# STORAGE.net
KiCad netlist of a schematic drawn in Altium Designer
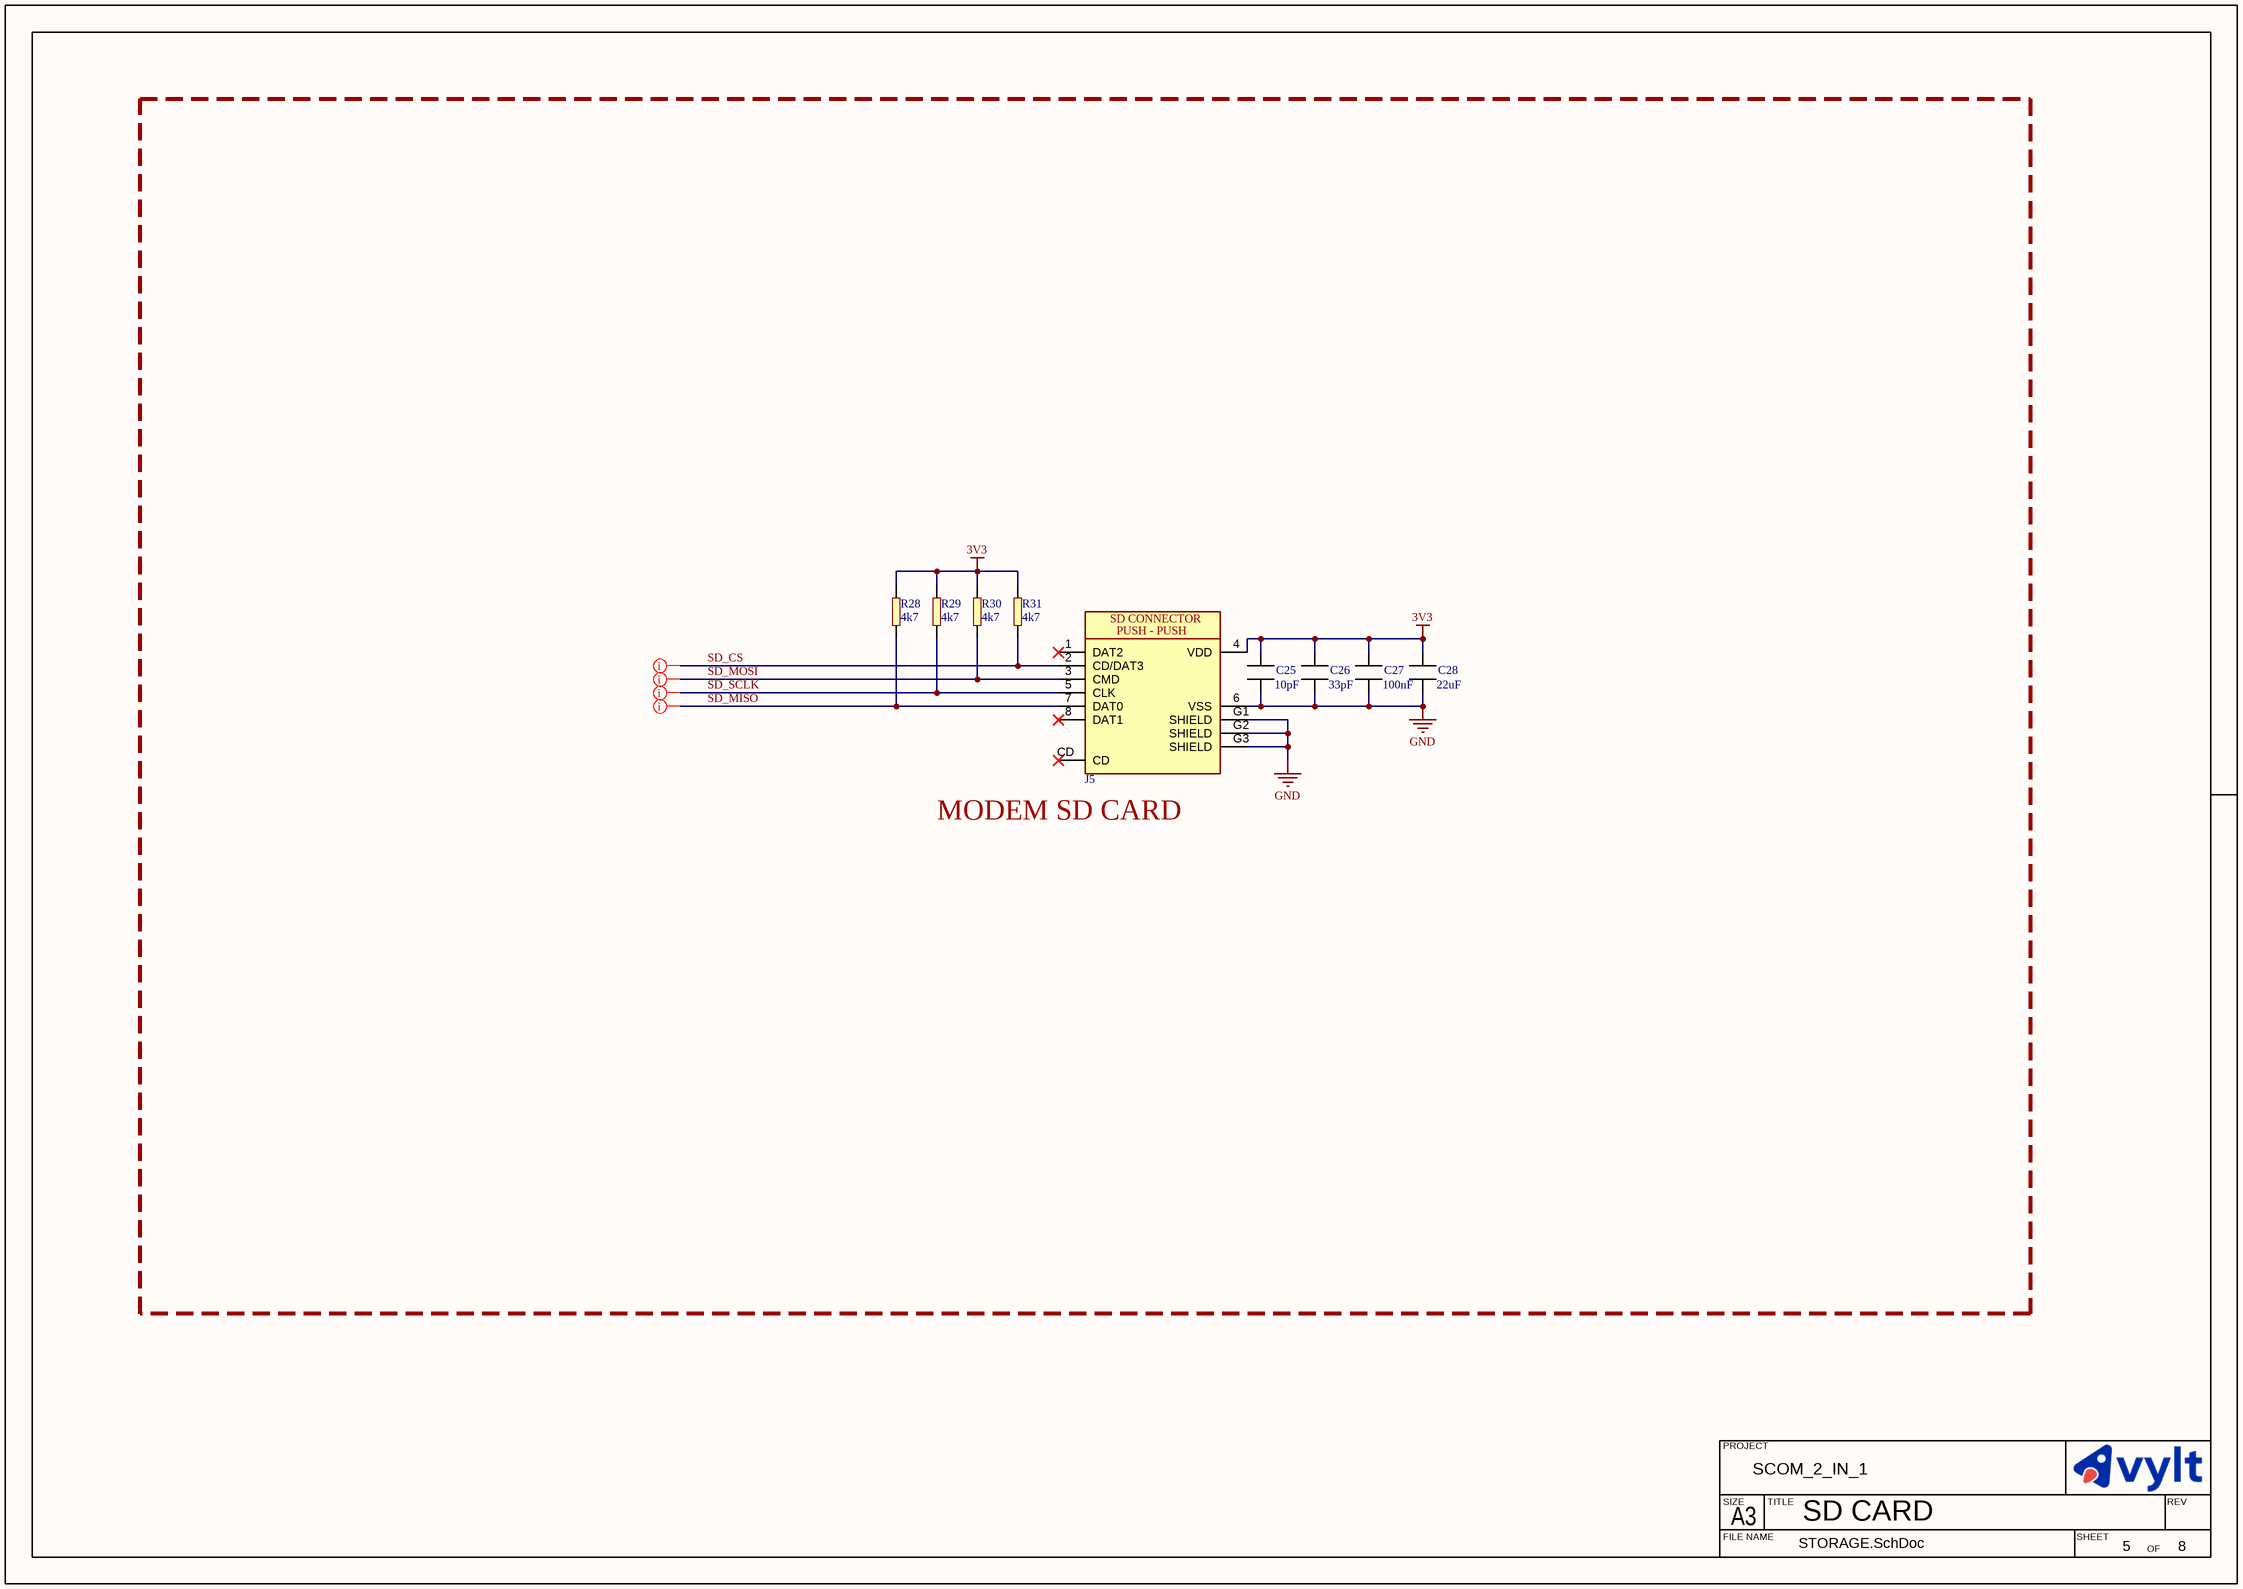
[diagram p0: STORAGE.SchDoc]

(export (version "E")
  (design (tool "Eeschema 10.0.6"))
  (components
    (comp (ref "C25")
      (value "10pF")
      (footprint "CAPC2012X13L")
      (description "Chip Capacitor, 2-Leads, Body 2.00x1.25mm, IPC High Density")
      (fields (field (name "Comment") "MLCC_0805"))
      (libsource (lib "Capacitor") (part "MLCC_0805"))
    )
    (comp (ref "C26")
      (value "33pF")
      (footprint "CAPC2012X13L")
      (description "Chip Capacitor, 2-Leads, Body 2.00x1.25mm, IPC High Density")
      (fields (field (name "Comment") "MLCC_0805"))
      (libsource (lib "Capacitor") (part "MLCC_0805"))
    )
    (comp (ref "C27")
      (value "100nF")
      (footprint "CAPC2012X13L")
      (description "Chip Capacitor, 2-Leads, Body 2.00x1.25mm, IPC High Density")
      (fields (field (name "Comment") "MLCC_0805"))
      (libsource (lib "Capacitor") (part "MLCC_0805"))
    )
    (comp (ref "C28")
      (value "22uF")
      (footprint "CAPC2012X13L")
      (description "Chip Capacitor, 2-Leads, Body 2.00x1.25mm, IPC High Density")
      (fields (field (name "Comment") "MLCC_0805"))
      (libsource (lib "Capacitor") (part "MLCC_0805"))
    )
    (comp (ref "J5")
      (value "GTFP084")
      (footprint "GTFP084")
      (description "9 (8 + 1) Position Card Connector Secure Digital - microSD™ Surface Mount, Right Angle Gold")
      (libsource (lib "Connectors") (part "GTFP084"))
    )
    (comp (ref "R28")
      (value "4k7")
      (footprint "RES_0603")
      (description "RES_0603")
      (fields (field (name "Comment") "ERP_101-1"))
      (libsource (lib "Resistor") (part "RES_0603"))
    )
    (comp (ref "R29")
      (value "4k7")
      (footprint "RES_0603")
      (description "RES_0603")
      (fields (field (name "Comment") "ERP_101-1"))
      (libsource (lib "Resistor") (part "RES_0603"))
    )
    (comp (ref "R30")
      (value "4k7")
      (footprint "RES_0603")
      (description "RES_0603")
      (fields (field (name "Comment") "ERP_101-1"))
      (libsource (lib "Resistor") (part "RES_0603"))
    )
    (comp (ref "R31")
      (value "4k7")
      (footprint "RES_0603")
      (description "RES_0603")
      (fields (field (name "Comment") "ERP_101-1"))
      (libsource (lib "Resistor") (part "RES_0603"))
    )
  )
  (nets
    (net (code "1") (name "/SD_CS") (class "Default")
      (node (ref "J5") (pin "2") (pinfunction "CD/DAT3_2") (pintype "passive"))
      (node (ref "R31") (pin "1") (pinfunction "1_1") (pintype "passive"))
    )
    (net (code "2") (name "/SD_MISO") (class "Default")
      (node (ref "J5") (pin "7") (pinfunction "DAT0_7") (pintype "passive"))
      (node (ref "R28") (pin "1") (pinfunction "1_1") (pintype "passive"))
    )
    (net (code "3") (name "/SD_MOSI") (class "Default")
      (node (ref "J5") (pin "3") (pinfunction "CMD_3") (pintype "passive"))
      (node (ref "R30") (pin "1") (pinfunction "1_1") (pintype "passive"))
    )
    (net (code "4") (name "/SD_SCLK") (class "Default")
      (node (ref "J5") (pin "5") (pinfunction "CLK_5") (pintype "passive"))
      (node (ref "R29") (pin "1") (pinfunction "1_1") (pintype "passive"))
    )
    (net (code "5") (name "3V3") (class "Default")
      (node (ref "C25") (pin "1") (pinfunction "1_1") (pintype "passive"))
      (node (ref "C26") (pin "1") (pinfunction "1_1") (pintype "passive"))
      (node (ref "C27") (pin "1") (pinfunction "1_1") (pintype "passive"))
      (node (ref "C28") (pin "1") (pinfunction "1_1") (pintype "passive"))
      (node (ref "J5") (pin "4") (pinfunction "VDD_4") (pintype "passive"))
      (node (ref "R28") (pin "2") (pinfunction "2_2") (pintype "passive"))
      (node (ref "R29") (pin "2") (pinfunction "2_2") (pintype "passive"))
      (node (ref "R30") (pin "2") (pinfunction "2_2") (pintype "passive"))
      (node (ref "R31") (pin "2") (pinfunction "2_2") (pintype "passive"))
    )
    (net (code "6") (name "GND") (class "Default")
      (node (ref "C25") (pin "2") (pinfunction "2_2") (pintype "passive"))
      (node (ref "C26") (pin "2") (pinfunction "2_2") (pintype "passive"))
      (node (ref "C27") (pin "2") (pinfunction "2_2") (pintype "passive"))
      (node (ref "C28") (pin "2") (pinfunction "2_2") (pintype "passive"))
      (node (ref "J5") (pin "6") (pinfunction "VSS_6") (pintype "power_in"))
      (node (ref "J5") (pin "G1") (pinfunction "SHIELD_G1") (pintype "power_in"))
      (node (ref "J5") (pin "G2") (pinfunction "SHIELD_G2") (pintype "power_in"))
      (node (ref "J5") (pin "G3") (pinfunction "SHIELD_G3") (pintype "power_in"))
    )
    (net (code "7") (name "unconnected-(J5-DAT1-Pad8)") (class "Default")
      (node (ref "J5") (pin "8") (pinfunction "DAT1_8") (pintype "passive+no_connect"))
    )
    (net (code "8") (name "unconnected-(J5-DAT2-Pad1)") (class "Default")
      (node (ref "J5") (pin "1") (pinfunction "DAT2_1") (pintype "passive+no_connect"))
    )
    (net (code "9") (name "unconnected-(J5-PadCD)") (class "Default")
      (node (ref "J5") (pin "CD") (pinfunction "CD_CD") (pintype "passive+no_connect"))
    )
  )
)
